# FLYBACK_SWITCHING_POWER_SUPPLY.net
KiCad netlist of a schematic drawn in Altium Designer
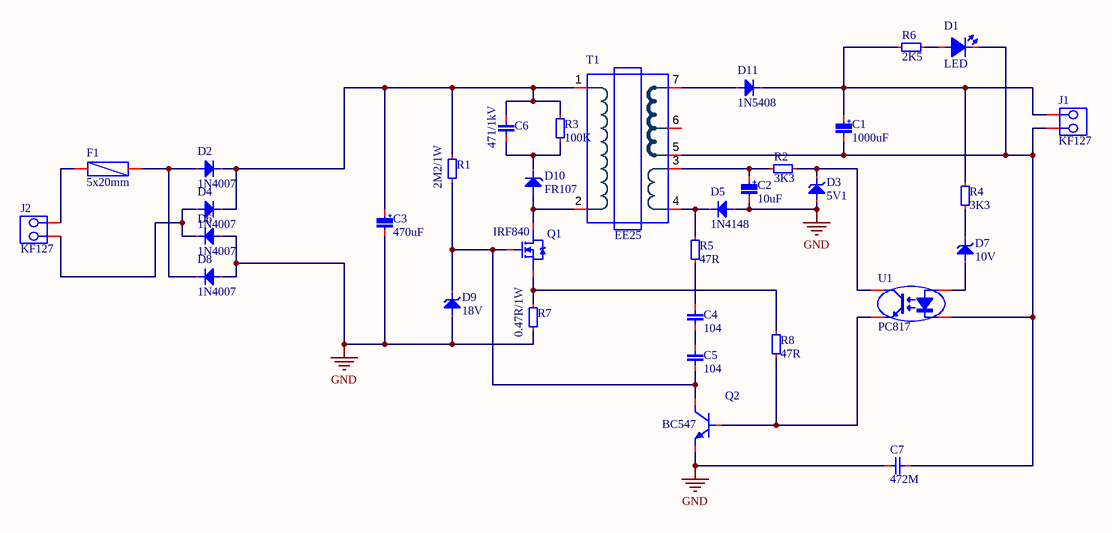
[diagram p0: FLYBACK_SWITCHING_POWER_SUPPLY.SchDoc]

(export (version "E")
  (design (tool "Eeschema 10.0.6"))
  (components
    (comp (ref "C1")
      (value "1000uF")
      (footprint "CAP_RAD_D12.5x15")
      (libsource (lib "MyAltiumLibrary") (part "Capacitor(Radian)"))
    )
    (comp (ref "C2")
      (value "10uF")
      (footprint "CAP_RAD_D05x11")
      (libsource (lib "MyAltiumLibrary") (part "Capacitor(Radian)"))
    )
    (comp (ref "C3")
      (value "470uF")
      (footprint "CAP_RAD_D12.5x15")
      (libsource (lib "MyAltiumLibrary") (part "Capacitor(Radian)"))
    )
    (comp (ref "C4")
      (value "104")
      (footprint "CAP_Ceramic_2.5MM")
      (libsource (lib "MyAltiumLibrary") (part "Capacitors(Disc)"))
    )
    (comp (ref "C5")
      (value "104")
      (footprint "CAP_Ceramic_2.5MM")
      (libsource (lib "MyAltiumLibrary") (part "Capacitors(Disc)"))
    )
    (comp (ref "C6")
      (value "471/1kV")
      (footprint "CAP_Ceramic_5MM")
      (libsource (lib "MyAltiumLibrary") (part "Capacitors(Disc)"))
    )
    (comp (ref "C7")
      (value "472M")
      (footprint "CAP_Ceramic_472M_7.21MM")
      (libsource (lib "") (part "Capacitors(Disc)_1"))
    )
    (comp (ref "D1")
      (value "LED")
      (footprint "LED_3MM_GREEN")
      (libsource (lib "MyAltiumLibrary") (part "LED 3MM"))
    )
    (comp (ref "D2")
      (value "1N4007")
      (footprint "DO-204AL-BK")
      (libsource (lib "MyAltiumLibrary") (part "Diode-1N4007"))
    )
    (comp (ref "D3")
      (value "5V1")
      (footprint "DO-204AL-RD")
      (libsource (lib "MyAltiumLibrary") (part "Diode-Zener"))
    )
    (comp (ref "D4")
      (value "1N4007")
      (footprint "DO-204AL-BK")
      (libsource (lib "MyAltiumLibrary") (part "Diode-1N4007"))
    )
    (comp (ref "D5")
      (value "1N4148")
      (footprint "DO-204AH-RD")
      (libsource (lib "MyAltiumLibrary") (part "Diode-1N4148"))
    )
    (comp (ref "D6")
      (value "1N4007")
      (footprint "DO-204AL-BK")
      (libsource (lib "MyAltiumLibrary") (part "Diode-1N4007"))
    )
    (comp (ref "D7")
      (value "10V")
      (footprint "DO-204AL-RD")
      (libsource (lib "MyAltiumLibrary") (part "Diode-Zener"))
    )
    (comp (ref "D8")
      (value "1N4007")
      (footprint "DO-204AL-BK")
      (libsource (lib "MyAltiumLibrary") (part "Diode-1N4007"))
    )
    (comp (ref "D9")
      (value "18V")
      (footprint "DO-204AL-RD")
      (libsource (lib "MyAltiumLibrary") (part "Diode-Zener"))
    )
    (comp (ref "D10")
      (value "FR107")
      (footprint "DO-204AL-BK")
      (description "1A 1000V")
      (libsource (lib "MyAltiumLibrary") (part "Diode-FR107"))
    )
    (comp (ref "D11")
      (value "1N5408")
      (footprint "DO-201AD-BK")
      (libsource (lib "MyAltiumLibrary") (part "Diode-1N5401"))
    )
    (comp (ref "F1")
      (value "5x20mm")
      (footprint "FUSE_Bel_MJS")
      (libsource (lib "MyAltiumLibrary") (part "Fuse-5x20mm"))
    )
    (comp (ref "J1")
      (value "KF127")
      (footprint "DG127-5.0-02P-14-00AH")
      (libsource (lib "MyAltiumLibrary") (part "DG127-5.0-02P-14-00AH"))
    )
    (comp (ref "J2")
      (value "KF127")
      (footprint "DG127-5.0-02P-14-00AH")
      (libsource (lib "") (part "DG127-5.0-02P-14-00AH_1"))
    )
    (comp (ref "Q1")
      (value "IRF840")
      (footprint "TO-220-HEAT-SINK-1")
      (libsource (lib "MyAltiumLibrary") (part "Mosfet-IRF840"))
    )
    (comp (ref "Q2")
      (value "BC547")
      (footprint "TO-92")
      (description "VCEO: 45 Vdc\r\nVCBO: 50 Vdc\r\nVEBO: 6.0 Vdc")
      (libsource (lib "MyAltiumLibrary") (part "Transistor-BC547"))
    )
    (comp (ref "R1") (value "2M2/1W") (footprint "RES-1W-H") (libsource (lib "") (part "Resistors THD_1")))
    (comp (ref "R2") (value "3K3") (footprint "RES-0.25W-H") (libsource (lib "") (part "Resistors THD_2")))
    (comp (ref "R3") (value "100K") (footprint "RES-0.5W-H") (libsource (lib "") (part "Resistors THD_1")))
    (comp (ref "R4") (value "3K3") (footprint "RES-0.25W-H") (libsource (lib "") (part "Resistors THD_1")))
    (comp (ref "R5") (value "47R") (footprint "RES-0.25W-H") (libsource (lib "") (part "Resistors THD_1")))
    (comp (ref "R6")
      (value "2K5")
      (footprint "RES-0.25W-H")
      (libsource (lib "MyAltiumLibrary") (part "Resistors THD"))
    )
    (comp (ref "R7") (value "0.47R/1W") (footprint "RES-2W-H") (libsource (lib "") (part "Resistors THD_1")))
    (comp (ref "R8") (value "47R") (footprint "RES-0.25W-H") (libsource (lib "") (part "Resistors THD_1")))
    (comp (ref "T1")
      (value "EE25")
      (footprint "TRANSFORMER-FLUOLAMP-8W")
      (libsource (lib "MyAltiumLibrary") (part "TRANS-FLUOLAMP-V0"))
    )
    (comp (ref "U1")
      (value "PC817")
      (footprint "PC817-DIP")
      (libsource (lib "MyAltiumLibrary") (part "Opto-PC817"))
    )
  )
  (nets
    (net (code "1") (name "GND") (class "Default")
      (node (ref "C2") (pin "2") (pinfunction "2_2") (pintype "passive"))
      (node (ref "C3") (pin "2") (pinfunction "2_2") (pintype "passive"))
      (node (ref "C7") (pin "1") (pinfunction "1_1") (pintype "passive"))
      (node (ref "D3") (pin "1") (pinfunction "1_1") (pintype "passive"))
      (node (ref "D5") (pin "1") (pinfunction "1_1") (pintype "passive"))
      (node (ref "D6") (pin "1") (pinfunction "1_1") (pintype "passive"))
      (node (ref "D8") (pin "1") (pinfunction "1_1") (pintype "passive"))
      (node (ref "D9") (pin "1") (pinfunction "1_1") (pintype "passive"))
      (node (ref "Q2") (pin "3") (pinfunction "E_3") (pintype "passive"))
      (node (ref "R7") (pin "1") (pinfunction "1_1") (pintype "passive"))
    )
    (net (code "2") (name "Net-(C1-Pad1)") (class "Default")
      (node (ref "C1") (pin "1") (pinfunction "1_1") (pintype "passive"))
      (node (ref "D11") (pin "2") (pinfunction "2_2") (pintype "passive"))
      (node (ref "J1") (pin "1") (pinfunction "1_1") (pintype "passive"))
      (node (ref "R4") (pin "2") (pinfunction "2_2") (pintype "passive"))
      (node (ref "R6") (pin "1") (pinfunction "1_1") (pintype "passive"))
    )
    (net (code "3") (name "Net-(C2-Pad1)") (class "Default")
      (node (ref "C2") (pin "1") (pinfunction "1_1") (pintype "passive"))
      (node (ref "R2") (pin "2") (pinfunction "2_2") (pintype "passive"))
      (node (ref "T1") (pin "3") (pinfunction "3_3") (pintype "passive"))
    )
    (net (code "4") (name "Net-(C3-Pad1)") (class "Default")
      (node (ref "C3") (pin "1") (pinfunction "1_1") (pintype "passive"))
      (node (ref "C6") (pin "2") (pinfunction "2_2") (pintype "passive"))
      (node (ref "D2") (pin "2") (pinfunction "2_2") (pintype "passive"))
      (node (ref "D4") (pin "2") (pinfunction "2_2") (pintype "passive"))
      (node (ref "R1") (pin "2") (pinfunction "2_2") (pintype "passive"))
      (node (ref "R3") (pin "2") (pinfunction "2_2") (pintype "passive"))
      (node (ref "T1") (pin "1") (pinfunction "1_1") (pintype "passive"))
    )
    (net (code "5") (name "Net-(C4-Pad1)") (class "Default")
      (node (ref "C4") (pin "1") (pinfunction "1_1") (pintype "passive"))
      (node (ref "C5") (pin "2") (pinfunction "2_2") (pintype "passive"))
    )
    (net (code "6") (name "Net-(C4-Pad2)") (class "Default")
      (node (ref "C4") (pin "2") (pinfunction "2_2") (pintype "passive"))
      (node (ref "R5") (pin "1") (pinfunction "1_1") (pintype "passive"))
    )
    (net (code "7") (name "Net-(C6-Pad1)") (class "Default")
      (node (ref "C6") (pin "1") (pinfunction "1_1") (pintype "passive"))
      (node (ref "D10") (pin "2") (pinfunction "2_2") (pintype "passive"))
      (node (ref "R3") (pin "1") (pinfunction "1_1") (pintype "passive"))
    )
    (net (code "8") (name "Net-(D1-A)") (class "Default")
      (node (ref "D1") (pin "1") (pinfunction "A_1") (pintype "passive"))
      (node (ref "R6") (pin "2") (pinfunction "2_2") (pintype "passive"))
    )
    (net (code "9") (name "Net-(D1-K)") (class "Default")
      (node (ref "C1") (pin "2") (pinfunction "2_2") (pintype "passive"))
      (node (ref "C7") (pin "2") (pinfunction "2_2") (pintype "passive"))
      (node (ref "D1") (pin "2") (pinfunction "K_2") (pintype "passive"))
      (node (ref "J1") (pin "2") (pinfunction "2_2") (pintype "passive"))
      (node (ref "T1") (pin "5") (pinfunction "5_5") (pintype "passive"))
      (node (ref "U1") (pin "2") (pinfunction "K_2") (pintype "passive"))
    )
    (net (code "10") (name "Net-(D2-Pad1)") (class "Default")
      (node (ref "D2") (pin "1") (pinfunction "1_1") (pintype "passive"))
      (node (ref "D8") (pin "2") (pinfunction "2_2") (pintype "passive"))
      (node (ref "F1") (pin "2") (pinfunction "2_2") (pintype "passive"))
    )
    (net (code "11") (name "Net-(D4-Pad1)") (class "Default")
      (node (ref "D4") (pin "1") (pinfunction "1_1") (pintype "passive"))
      (node (ref "D6") (pin "2") (pinfunction "2_2") (pintype "passive"))
      (node (ref "J2") (pin "1") (pinfunction "1_1") (pintype "passive"))
    )
    (net (code "12") (name "Net-(D5-Pad2)") (class "Default")
      (node (ref "D5") (pin "2") (pinfunction "2_2") (pintype "passive"))
      (node (ref "R5") (pin "2") (pinfunction "2_2") (pintype "passive"))
      (node (ref "T1") (pin "4") (pinfunction "4_4") (pintype "passive"))
    )
    (net (code "13") (name "Net-(D7-Pad2)") (class "Default")
      (node (ref "D7") (pin "2") (pinfunction "2_2") (pintype "passive"))
      (node (ref "R4") (pin "1") (pinfunction "1_1") (pintype "passive"))
    )
    (net (code "14") (name "Net-(D11-Pad1)") (class "Default")
      (node (ref "D11") (pin "1") (pinfunction "1_1") (pintype "passive"))
      (node (ref "T1") (pin "7") (pinfunction "7_7") (pintype "passive"))
    )
    (net (code "15") (name "Net-(F1-Pad1)") (class "Default")
      (node (ref "F1") (pin "1") (pinfunction "1_1") (pintype "passive"))
      (node (ref "J2") (pin "2") (pinfunction "2_2") (pintype "passive"))
    )
    (net (code "16") (name "Net-(Q1-D)") (class "Default")
      (node (ref "D10") (pin "1") (pinfunction "1_1") (pintype "passive"))
      (node (ref "Q1") (pin "2") (pinfunction "D_2") (pintype "passive"))
      (node (ref "T1") (pin "2") (pinfunction "2_2") (pintype "passive"))
    )
    (net (code "17") (name "Net-(Q1-G)") (class "Default")
      (node (ref "C5") (pin "1") (pinfunction "1_1") (pintype "passive"))
      (node (ref "D9") (pin "2") (pinfunction "2_2") (pintype "passive"))
      (node (ref "Q1") (pin "1") (pinfunction "G_1") (pintype "passive"))
      (node (ref "Q2") (pin "1") (pinfunction "C_1") (pintype "passive"))
      (node (ref "R1") (pin "1") (pinfunction "1_1") (pintype "passive"))
    )
    (net (code "18") (name "Net-(Q1-S)") (class "Default")
      (node (ref "Q1") (pin "3") (pinfunction "S_3") (pintype "passive"))
      (node (ref "R7") (pin "2") (pinfunction "2_2") (pintype "passive"))
      (node (ref "R8") (pin "2") (pinfunction "2_2") (pintype "passive"))
    )
    (net (code "19") (name "Net-(Q2-B)") (class "Default")
      (node (ref "Q2") (pin "2") (pinfunction "B_2") (pintype "passive"))
      (node (ref "R8") (pin "1") (pinfunction "1_1") (pintype "passive"))
      (node (ref "U1") (pin "3") (pinfunction "E_3") (pintype "passive"))
    )
    (net (code "20") (name "Net-(U1-A)") (class "Default")
      (node (ref "D7") (pin "1") (pinfunction "1_1") (pintype "passive"))
      (node (ref "U1") (pin "1") (pinfunction "A_1") (pintype "passive"))
    )
    (net (code "21") (name "Net-(U1-C)") (class "Default")
      (node (ref "D3") (pin "2") (pinfunction "2_2") (pintype "passive"))
      (node (ref "R2") (pin "1") (pinfunction "1_1") (pintype "passive"))
      (node (ref "U1") (pin "4") (pinfunction "C_4") (pintype "passive"))
    )
    (net (code "22") (name "unconnected-(T1-Pad6)") (class "Default")
      (node (ref "T1") (pin "6") (pinfunction "6_6") (pintype "passive"))
    )
  )
)
